# RaspiLink_bk1.net
KiCad netlist of a schematic drawn in EAGLE
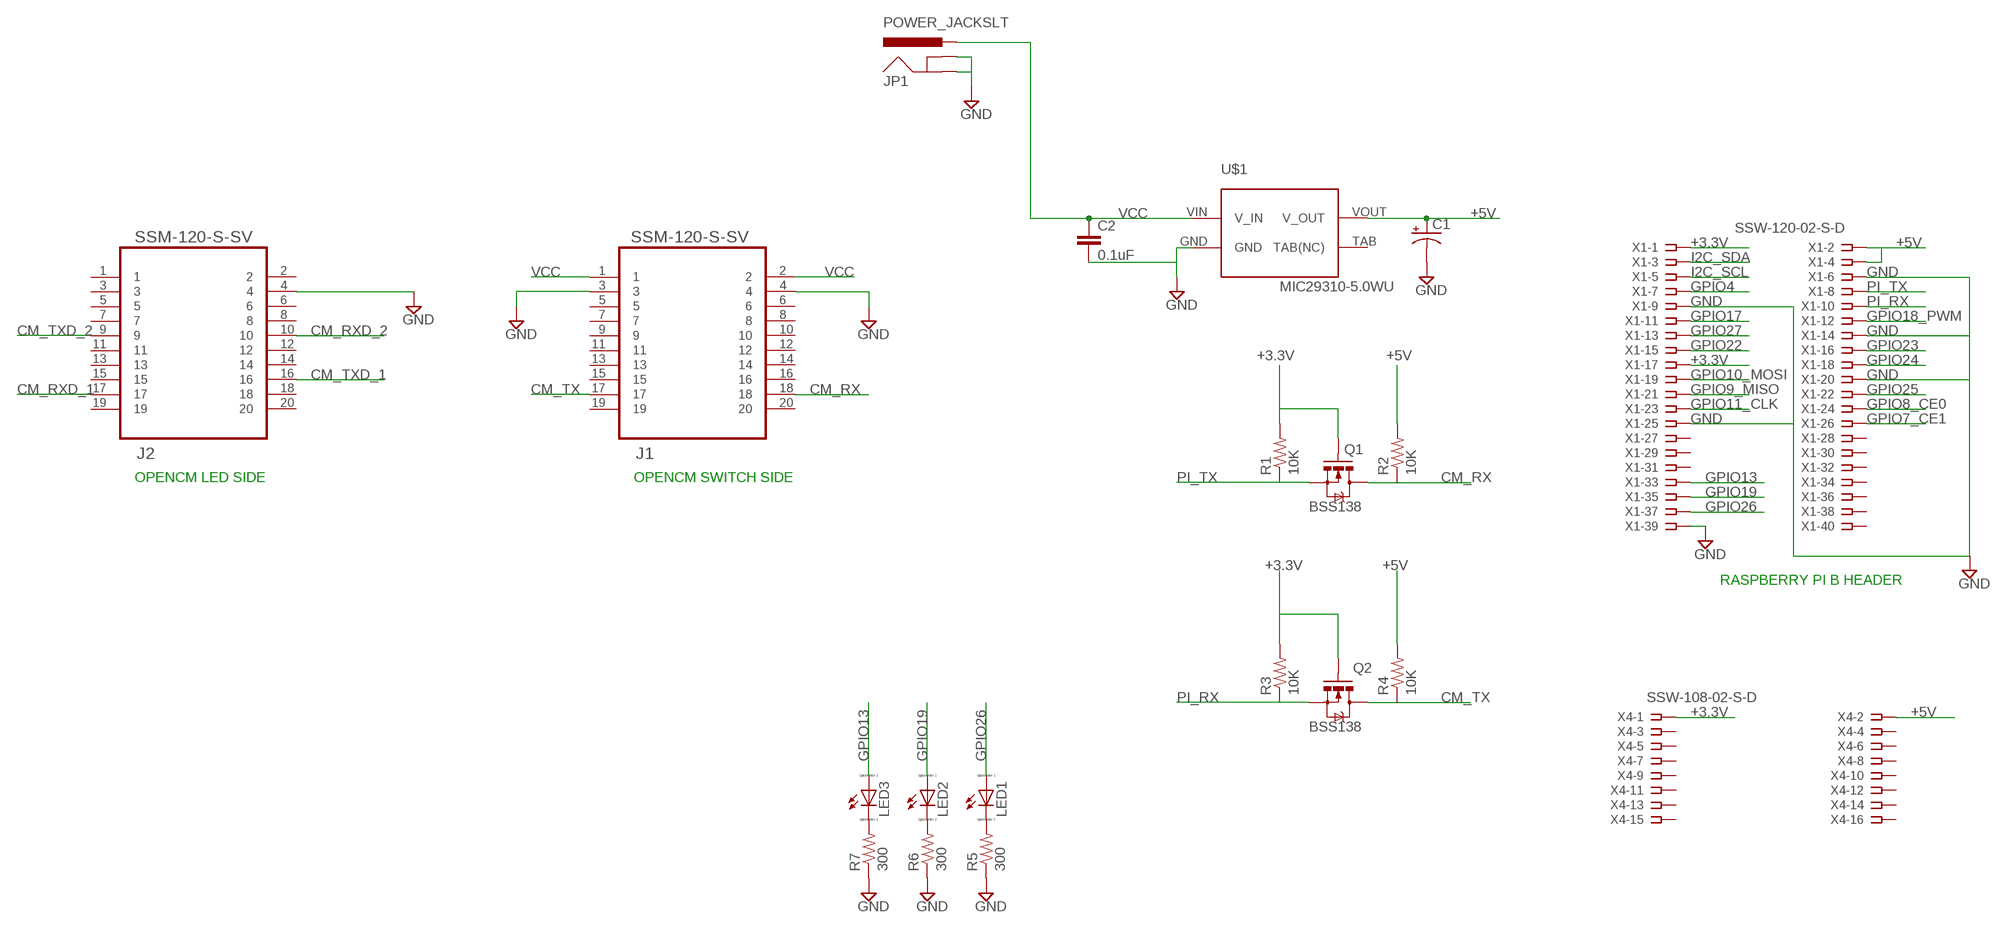
[diagram p0: schematic, sheet 1]

(export (version "E")
  (design (tool "Eeschema 10.0.6"))
  (components
    (comp (ref "C1")
      (value "100UF-25V-20%(PTH)")
      (footprint "eagle-import:CPOL-RADIAL-100UF-25V")
      (libsource (lib "eagle-import") (part "100UF-25V-20%(PTH)"))
    )
    (comp (ref "C2")
      (value "0.1uF")
      (footprint "eagle-import:0603-CAP")
      (libsource (lib "eagle-import") (part "0.1UF-25V-5%(0603)"))
    )
    (comp (ref "J1")
      (value "SSM-120-S-SV")
      (footprint "eagle-import:SAMTEC_SSM-120-S-SV")
      (libsource (lib "eagle-import") (part "SSM-120-S-SV"))
    )
    (comp (ref "J2")
      (value "SSM-120-S-SV")
      (footprint "eagle-import:SAMTEC_SSM-120-S-SV")
      (libsource (lib "eagle-import") (part "SSM-120-S-SV"))
    )
    (comp (ref "JP1")
      (value "POWER_JACKSLT")
      (footprint "eagle-import:POWER_JACK_SLOT")
      (libsource (lib "eagle-import") (part "POWER_JACKSLT"))
    )
    (comp (ref "LED1")
      (value "LED_ELD260")
      (footprint "eagle-import:LED_LD260")
      (libsource (lib "eagle-import") (part "LED_ELD260"))
    )
    (comp (ref "LED2")
      (value "LED_ELD260")
      (footprint "eagle-import:LED_LD260")
      (libsource (lib "eagle-import") (part "LED_ELD260"))
    )
    (comp (ref "LED3")
      (value "LED_ELD260")
      (footprint "eagle-import:LED_LD260")
      (libsource (lib "eagle-import") (part "LED_ELD260"))
    )
    (comp (ref "Q1")
      (value "MOSFET-NCHANNELBSS123LT1G")
      (footprint "eagle-import:SOT23-3")
      (fields (field (name "PROD_ID") "TRANS-08345") (field (name "PROD_ID_1") "BSS138"))
      (libsource (lib "eagle-import") (part "MOSFET-NCHANNELBSS123LT1G"))
    )
    (comp (ref "Q2")
      (value "MOSFET-NCHANNELBSS123LT1G")
      (footprint "eagle-import:SOT23-3")
      (fields (field (name "PROD_ID") "TRANS-08345") (field (name "PROD_ID_1") "BSS138"))
      (libsource (lib "eagle-import") (part "MOSFET-NCHANNELBSS123LT1G"))
    )
    (comp (ref "R1")
      (value "10K")
      (footprint "eagle-import:0603-RES")
      (libsource (lib "eagle-import") (part "RESISTOR0603-RES"))
    )
    (comp (ref "R2")
      (value "10K")
      (footprint "eagle-import:0603-RES")
      (libsource (lib "eagle-import") (part "RESISTOR0603-RES"))
    )
    (comp (ref "R3")
      (value "10K")
      (footprint "eagle-import:0603-RES")
      (libsource (lib "eagle-import") (part "RESISTOR0603-RES"))
    )
    (comp (ref "R4")
      (value "10K")
      (footprint "eagle-import:0603-RES")
      (libsource (lib "eagle-import") (part "RESISTOR0603-RES"))
    )
    (comp (ref "R5")
      (value "300")
      (footprint "eagle-import:0603-RES")
      (libsource (lib "eagle-import") (part "RESISTOR0603-RES"))
    )
    (comp (ref "R6")
      (value "300")
      (footprint "eagle-import:0603-RES")
      (libsource (lib "eagle-import") (part "RESISTOR0603-RES"))
    )
    (comp (ref "R7")
      (value "300")
      (footprint "eagle-import:0603-RES")
      (libsource (lib "eagle-import") (part "RESISTOR0603-RES"))
    )
    (comp (ref "U$1")
      (value "MIC29310-5.0WU")
      (footprint "eagle-import:TO-263-3")
      (libsource (lib "eagle-import") (part "MIC29310-5.0WU"))
    )
    (comp (ref "X1")
      (value "SSW-120-02-S-D")
      (footprint "eagle-import:SSW-120-02-S-D")
      (libsource (lib "eagle-import") (part "SSW-120-02-S-D"))
    )
    (comp (ref "X4")
      (value "SSW-108-02-S-D")
      (footprint "eagle-import:SSW-108-02-S-D")
      (libsource (lib "eagle-import") (part "SSW-108-02-S-D"))
    )
  )
  (nets
    (net (code "1") (name "/+3.3V") (class "Default")
      (node (ref "Q1") (pin "1") (pinfunction "G_1") (pintype "passive"))
      (node (ref "Q2") (pin "1") (pinfunction "G_1") (pintype "passive"))
      (node (ref "R1") (pin "2") (pinfunction "2_2") (pintype "passive"))
      (node (ref "R3") (pin "2") (pinfunction "2_2") (pintype "passive"))
      (node (ref "X1") (pin "1") (pinfunction "1_1") (pintype "passive"))
      (node (ref "X1") (pin "17") (pinfunction "1_17") (pintype "passive"))
      (node (ref "X4") (pin "1") (pinfunction "1_1") (pintype "passive"))
    )
    (net (code "2") (name "/+5V") (class "Default")
      (node (ref "C1") (pin "1") (pinfunction "+_1") (pintype "passive"))
      (node (ref "R2") (pin "2") (pinfunction "2_2") (pintype "passive"))
      (node (ref "R4") (pin "2") (pinfunction "2_2") (pintype "passive"))
      (node (ref "U$1") (pin "VOUT") (pinfunction "V_OUT_VOUT") (pintype "bidirectional"))
      (node (ref "X1") (pin "2") (pinfunction "1_2") (pintype "passive"))
      (node (ref "X1") (pin "4") (pinfunction "1_4") (pintype "passive"))
      (node (ref "X4") (pin "2") (pinfunction "1_2") (pintype "passive"))
    )
    (net (code "3") (name "/CM_RX") (class "Default")
      (node (ref "J1") (pin "18") (pinfunction "18_18") (pintype "passive"))
      (node (ref "Q1") (pin "3") (pinfunction "D_3") (pintype "passive"))
      (node (ref "R2") (pin "1") (pinfunction "1_1") (pintype "passive"))
    )
    (net (code "4") (name "/CM_RXD_1") (class "Default")
      (node (ref "J2") (pin "17") (pinfunction "17_17") (pintype "passive"))
    )
    (net (code "5") (name "/CM_RXD_2") (class "Default")
      (node (ref "J2") (pin "10") (pinfunction "10_10") (pintype "passive"))
    )
    (net (code "6") (name "/CM_TX") (class "Default")
      (node (ref "J1") (pin "17") (pinfunction "17_17") (pintype "passive"))
      (node (ref "Q2") (pin "3") (pinfunction "D_3") (pintype "passive"))
      (node (ref "R4") (pin "1") (pinfunction "1_1") (pintype "passive"))
    )
    (net (code "7") (name "/CM_TXD_1") (class "Default")
      (node (ref "J2") (pin "16") (pinfunction "16_16") (pintype "passive"))
    )
    (net (code "8") (name "/CM_TXD_2") (class "Default")
      (node (ref "J2") (pin "9") (pinfunction "9_9") (pintype "passive"))
    )
    (net (code "9") (name "/GPIO4") (class "Default")
      (node (ref "X1") (pin "7") (pinfunction "1_7") (pintype "passive"))
    )
    (net (code "10") (name "/GPIO7_CE1") (class "Default")
      (node (ref "X1") (pin "26") (pinfunction "1_26") (pintype "passive"))
    )
    (net (code "11") (name "/GPIO8_CE0") (class "Default")
      (node (ref "X1") (pin "24") (pinfunction "1_24") (pintype "passive"))
    )
    (net (code "12") (name "/GPIO9_MISO") (class "Default")
      (node (ref "X1") (pin "21") (pinfunction "1_21") (pintype "passive"))
    )
    (net (code "13") (name "/GPIO10_MOSI") (class "Default")
      (node (ref "X1") (pin "19") (pinfunction "1_19") (pintype "passive"))
    )
    (net (code "14") (name "/GPIO11_CLK") (class "Default")
      (node (ref "X1") (pin "23") (pinfunction "1_23") (pintype "passive"))
    )
    (net (code "15") (name "/GPIO13") (class "Default")
      (node (ref "LED3") (pin "A") (pinfunction "A_A") (pintype "passive"))
      (node (ref "X1") (pin "33") (pinfunction "1_33") (pintype "passive"))
    )
    (net (code "16") (name "/GPIO17") (class "Default")
      (node (ref "X1") (pin "11") (pinfunction "1_11") (pintype "passive"))
    )
    (net (code "17") (name "/GPIO18_PWM") (class "Default")
      (node (ref "X1") (pin "12") (pinfunction "1_12") (pintype "passive"))
    )
    (net (code "18") (name "/GPIO19") (class "Default")
      (node (ref "LED2") (pin "A") (pinfunction "A_A") (pintype "passive"))
      (node (ref "X1") (pin "35") (pinfunction "1_35") (pintype "passive"))
    )
    (net (code "19") (name "/GPIO22") (class "Default")
      (node (ref "X1") (pin "15") (pinfunction "1_15") (pintype "passive"))
    )
    (net (code "20") (name "/GPIO23") (class "Default")
      (node (ref "X1") (pin "16") (pinfunction "1_16") (pintype "passive"))
    )
    (net (code "21") (name "/GPIO24") (class "Default")
      (node (ref "X1") (pin "18") (pinfunction "1_18") (pintype "passive"))
    )
    (net (code "22") (name "/GPIO25") (class "Default")
      (node (ref "X1") (pin "22") (pinfunction "1_22") (pintype "passive"))
    )
    (net (code "23") (name "/GPIO26") (class "Default")
      (node (ref "LED1") (pin "A") (pinfunction "A_A") (pintype "passive"))
      (node (ref "X1") (pin "37") (pinfunction "1_37") (pintype "passive"))
    )
    (net (code "24") (name "/GPIO27") (class "Default")
      (node (ref "X1") (pin "13") (pinfunction "1_13") (pintype "passive"))
    )
    (net (code "25") (name "/I2C_SCL") (class "Default")
      (node (ref "X1") (pin "5") (pinfunction "1_5") (pintype "passive"))
    )
    (net (code "26") (name "/I2C_SDA") (class "Default")
      (node (ref "X1") (pin "3") (pinfunction "1_3") (pintype "passive"))
    )
    (net (code "27") (name "/PI_RX") (class "Default")
      (node (ref "Q2") (pin "2") (pinfunction "S_2") (pintype "passive"))
      (node (ref "R3") (pin "1") (pinfunction "1_1") (pintype "passive"))
      (node (ref "X1") (pin "10") (pinfunction "1_10") (pintype "passive"))
    )
    (net (code "28") (name "/PI_TX") (class "Default")
      (node (ref "Q1") (pin "2") (pinfunction "S_2") (pintype "passive"))
      (node (ref "R1") (pin "1") (pinfunction "1_1") (pintype "passive"))
      (node (ref "X1") (pin "8") (pinfunction "1_8") (pintype "passive"))
    )
    (net (code "29") (name "/VCC") (class "Default")
      (node (ref "C2") (pin "1") (pinfunction "1_1") (pintype "passive"))
      (node (ref "J1") (pin "1") (pinfunction "1_1") (pintype "passive"))
      (node (ref "J1") (pin "2") (pinfunction "2_2") (pintype "passive"))
      (node (ref "JP1") (pin "PWR") (pinfunction "PWR_PWR") (pintype "bidirectional"))
      (node (ref "U$1") (pin "VIN") (pinfunction "V_IN_VIN") (pintype "bidirectional"))
    )
    (net (code "30") (name "GND") (class "Default")
      (node (ref "C1") (pin "2") (pinfunction "-_2") (pintype "passive"))
      (node (ref "C2") (pin "2") (pinfunction "2_2") (pintype "passive"))
      (node (ref "J1") (pin "3") (pinfunction "3_3") (pintype "passive"))
      (node (ref "J1") (pin "4") (pinfunction "4_4") (pintype "passive"))
      (node (ref "J2") (pin "4") (pinfunction "4_4") (pintype "passive"))
      (node (ref "JP1") (pin "GND@1") (pinfunction "GNDBREAK_GND@1") (pintype "bidirectional"))
      (node (ref "JP1") (pin "GND@2") (pinfunction "GND_GND@2") (pintype "bidirectional"))
      (node (ref "R5") (pin "1") (pinfunction "1_1") (pintype "passive"))
      (node (ref "R6") (pin "1") (pinfunction "1_1") (pintype "passive"))
      (node (ref "R7") (pin "1") (pinfunction "1_1") (pintype "passive"))
      (node (ref "U$1") (pin "GND") (pinfunction "GND_GND") (pintype "bidirectional"))
      (node (ref "X1") (pin "14") (pinfunction "1_14") (pintype "passive"))
      (node (ref "X1") (pin "20") (pinfunction "1_20") (pintype "passive"))
      (node (ref "X1") (pin "25") (pinfunction "1_25") (pintype "passive"))
      (node (ref "X1") (pin "39") (pinfunction "1_39") (pintype "passive"))
      (node (ref "X1") (pin "6") (pinfunction "1_6") (pintype "passive"))
      (node (ref "X1") (pin "9") (pinfunction "1_9") (pintype "passive"))
    )
    (net (code "31") (name "Net-(LED1-C)") (class "Default")
      (node (ref "LED1") (pin "K") (pinfunction "C_K") (pintype "passive"))
      (node (ref "R5") (pin "2") (pinfunction "2_2") (pintype "passive"))
    )
    (net (code "32") (name "Net-(LED2-C)") (class "Default")
      (node (ref "LED2") (pin "K") (pinfunction "C_K") (pintype "passive"))
      (node (ref "R6") (pin "2") (pinfunction "2_2") (pintype "passive"))
    )
    (net (code "33") (name "Net-(LED3-C)") (class "Default")
      (node (ref "LED3") (pin "K") (pinfunction "C_K") (pintype "passive"))
      (node (ref "R7") (pin "2") (pinfunction "2_2") (pintype "passive"))
    )
    (net (code "34") (name "unconnected-(J1-Pad5)") (class "Default")
      (node (ref "J1") (pin "5") (pinfunction "5_5") (pintype "passive"))
    )
    (net (code "35") (name "unconnected-(J1-Pad6)") (class "Default")
      (node (ref "J1") (pin "6") (pinfunction "6_6") (pintype "passive"))
    )
    (net (code "36") (name "unconnected-(J1-Pad7)") (class "Default")
      (node (ref "J1") (pin "7") (pinfunction "7_7") (pintype "passive"))
    )
    (net (code "37") (name "unconnected-(J1-Pad8)") (class "Default")
      (node (ref "J1") (pin "8") (pinfunction "8_8") (pintype "passive"))
    )
    (net (code "38") (name "unconnected-(J1-Pad9)") (class "Default")
      (node (ref "J1") (pin "9") (pinfunction "9_9") (pintype "passive"))
    )
    (net (code "39") (name "unconnected-(J1-Pad10)") (class "Default")
      (node (ref "J1") (pin "10") (pinfunction "10_10") (pintype "passive"))
    )
    (net (code "40") (name "unconnected-(J1-Pad11)") (class "Default")
      (node (ref "J1") (pin "11") (pinfunction "11_11") (pintype "passive"))
    )
    (net (code "41") (name "unconnected-(J1-Pad12)") (class "Default")
      (node (ref "J1") (pin "12") (pinfunction "12_12") (pintype "passive"))
    )
    (net (code "42") (name "unconnected-(J1-Pad13)") (class "Default")
      (node (ref "J1") (pin "13") (pinfunction "13_13") (pintype "passive"))
    )
    (net (code "43") (name "unconnected-(J1-Pad14)") (class "Default")
      (node (ref "J1") (pin "14") (pinfunction "14_14") (pintype "passive"))
    )
    (net (code "44") (name "unconnected-(J1-Pad15)") (class "Default")
      (node (ref "J1") (pin "15") (pinfunction "15_15") (pintype "passive"))
    )
    (net (code "45") (name "unconnected-(J1-Pad16)") (class "Default")
      (node (ref "J1") (pin "16") (pinfunction "16_16") (pintype "passive"))
    )
    (net (code "46") (name "unconnected-(J1-Pad19)") (class "Default")
      (node (ref "J1") (pin "19") (pinfunction "19_19") (pintype "passive"))
    )
    (net (code "47") (name "unconnected-(J1-Pad20)") (class "Default")
      (node (ref "J1") (pin "20") (pinfunction "20_20") (pintype "passive"))
    )
    (net (code "48") (name "unconnected-(J2-Pad1)") (class "Default")
      (node (ref "J2") (pin "1") (pinfunction "1_1") (pintype "passive"))
    )
    (net (code "49") (name "unconnected-(J2-Pad2)") (class "Default")
      (node (ref "J2") (pin "2") (pinfunction "2_2") (pintype "passive"))
    )
    (net (code "50") (name "unconnected-(J2-Pad3)") (class "Default")
      (node (ref "J2") (pin "3") (pinfunction "3_3") (pintype "passive"))
    )
    (net (code "51") (name "unconnected-(J2-Pad5)") (class "Default")
      (node (ref "J2") (pin "5") (pinfunction "5_5") (pintype "passive"))
    )
    (net (code "52") (name "unconnected-(J2-Pad6)") (class "Default")
      (node (ref "J2") (pin "6") (pinfunction "6_6") (pintype "passive"))
    )
    (net (code "53") (name "unconnected-(J2-Pad7)") (class "Default")
      (node (ref "J2") (pin "7") (pinfunction "7_7") (pintype "passive"))
    )
    (net (code "54") (name "unconnected-(J2-Pad8)") (class "Default")
      (node (ref "J2") (pin "8") (pinfunction "8_8") (pintype "passive"))
    )
    (net (code "55") (name "unconnected-(J2-Pad11)") (class "Default")
      (node (ref "J2") (pin "11") (pinfunction "11_11") (pintype "passive"))
    )
    (net (code "56") (name "unconnected-(J2-Pad12)") (class "Default")
      (node (ref "J2") (pin "12") (pinfunction "12_12") (pintype "passive"))
    )
    (net (code "57") (name "unconnected-(J2-Pad13)") (class "Default")
      (node (ref "J2") (pin "13") (pinfunction "13_13") (pintype "passive"))
    )
    (net (code "58") (name "unconnected-(J2-Pad14)") (class "Default")
      (node (ref "J2") (pin "14") (pinfunction "14_14") (pintype "passive"))
    )
    (net (code "59") (name "unconnected-(J2-Pad15)") (class "Default")
      (node (ref "J2") (pin "15") (pinfunction "15_15") (pintype "passive"))
    )
    (net (code "60") (name "unconnected-(J2-Pad18)") (class "Default")
      (node (ref "J2") (pin "18") (pinfunction "18_18") (pintype "passive"))
    )
    (net (code "61") (name "unconnected-(J2-Pad19)") (class "Default")
      (node (ref "J2") (pin "19") (pinfunction "19_19") (pintype "passive"))
    )
    (net (code "62") (name "unconnected-(J2-Pad20)") (class "Default")
      (node (ref "J2") (pin "20") (pinfunction "20_20") (pintype "passive"))
    )
    (net (code "63") (name "unconnected-(U$1-TAB(NC)-PadTAB)") (class "Default")
      (node (ref "U$1") (pin "TAB") (pinfunction "TAB(NC)_TAB") (pintype "bidirectional"))
    )
    (net (code "64") (name "unconnected-(X1AB-1-Pad34)") (class "Default")
      (node (ref "X1") (pin "34") (pinfunction "1_34") (pintype "passive"))
    )
    (net (code "65") (name "unconnected-(X1AD-1-Pad36)") (class "Default")
      (node (ref "X1") (pin "36") (pinfunction "1_36") (pintype "passive"))
    )
    (net (code "66") (name "unconnected-(X1AF-1-Pad38)") (class "Default")
      (node (ref "X1") (pin "38") (pinfunction "1_38") (pintype "passive"))
    )
    (net (code "67") (name "unconnected-(X1AI-1-Pad40)") (class "Default")
      (node (ref "X1") (pin "40") (pinfunction "1_40") (pintype "passive"))
    )
    (net (code "68") (name "unconnected-(X1T-1-Pad27)") (class "Default")
      (node (ref "X1") (pin "27") (pinfunction "1_27") (pintype "passive"))
    )
    (net (code "69") (name "unconnected-(X1U-1-Pad28)") (class "Default")
      (node (ref "X1") (pin "28") (pinfunction "1_28") (pintype "passive"))
    )
    (net (code "70") (name "unconnected-(X1V-1-Pad29)") (class "Default")
      (node (ref "X1") (pin "29") (pinfunction "1_29") (pintype "passive"))
    )
    (net (code "71") (name "unconnected-(X1X-1-Pad30)") (class "Default")
      (node (ref "X1") (pin "30") (pinfunction "1_30") (pintype "passive"))
    )
    (net (code "72") (name "unconnected-(X1Y-1-Pad31)") (class "Default")
      (node (ref "X1") (pin "31") (pinfunction "1_31") (pintype "passive"))
    )
    (net (code "73") (name "unconnected-(X1Z-1-Pad32)") (class "Default")
      (node (ref "X1") (pin "32") (pinfunction "1_32") (pintype "passive"))
    )
    (net (code "74") (name "unconnected-(X4B-1-Pad10)") (class "Default")
      (node (ref "X4") (pin "10") (pinfunction "1_10") (pintype "passive"))
    )
    (net (code "75") (name "unconnected-(X4C-1-Pad11)") (class "Default")
      (node (ref "X4") (pin "11") (pinfunction "1_11") (pintype "passive"))
    )
    (net (code "76") (name "unconnected-(X4D-1-Pad12)") (class "Default")
      (node (ref "X4") (pin "12") (pinfunction "1_12") (pintype "passive"))
    )
    (net (code "77") (name "unconnected-(X4E-1-Pad13)") (class "Default")
      (node (ref "X4") (pin "13") (pinfunction "1_13") (pintype "passive"))
    )
    (net (code "78") (name "unconnected-(X4F-1-Pad14)") (class "Default")
      (node (ref "X4") (pin "14") (pinfunction "1_14") (pintype "passive"))
    )
    (net (code "79") (name "unconnected-(X4G-1-Pad15)") (class "Default")
      (node (ref "X4") (pin "15") (pinfunction "1_15") (pintype "passive"))
    )
    (net (code "80") (name "unconnected-(X4H-1-Pad16)") (class "Default")
      (node (ref "X4") (pin "16") (pinfunction "1_16") (pintype "passive"))
    )
    (net (code "81") (name "unconnected-(X4J-1-Pad3)") (class "Default")
      (node (ref "X4") (pin "3") (pinfunction "1_3") (pintype "passive"))
    )
    (net (code "82") (name "unconnected-(X4K-1-Pad4)") (class "Default")
      (node (ref "X4") (pin "4") (pinfunction "1_4") (pintype "passive"))
    )
    (net (code "83") (name "unconnected-(X4L-1-Pad5)") (class "Default")
      (node (ref "X4") (pin "5") (pinfunction "1_5") (pintype "passive"))
    )
    (net (code "84") (name "unconnected-(X4M-1-Pad6)") (class "Default")
      (node (ref "X4") (pin "6") (pinfunction "1_6") (pintype "passive"))
    )
    (net (code "85") (name "unconnected-(X4N-1-Pad7)") (class "Default")
      (node (ref "X4") (pin "7") (pinfunction "1_7") (pintype "passive"))
    )
    (net (code "86") (name "unconnected-(X4O-1-Pad8)") (class "Default")
      (node (ref "X4") (pin "8") (pinfunction "1_8") (pintype "passive"))
    )
    (net (code "87") (name "unconnected-(X4P-1-Pad9)") (class "Default")
      (node (ref "X4") (pin "9") (pinfunction "1_9") (pintype "passive"))
    )
  )
)
